# Marshmallow.net
KiCad netlist of a schematic drawn in EAGLE
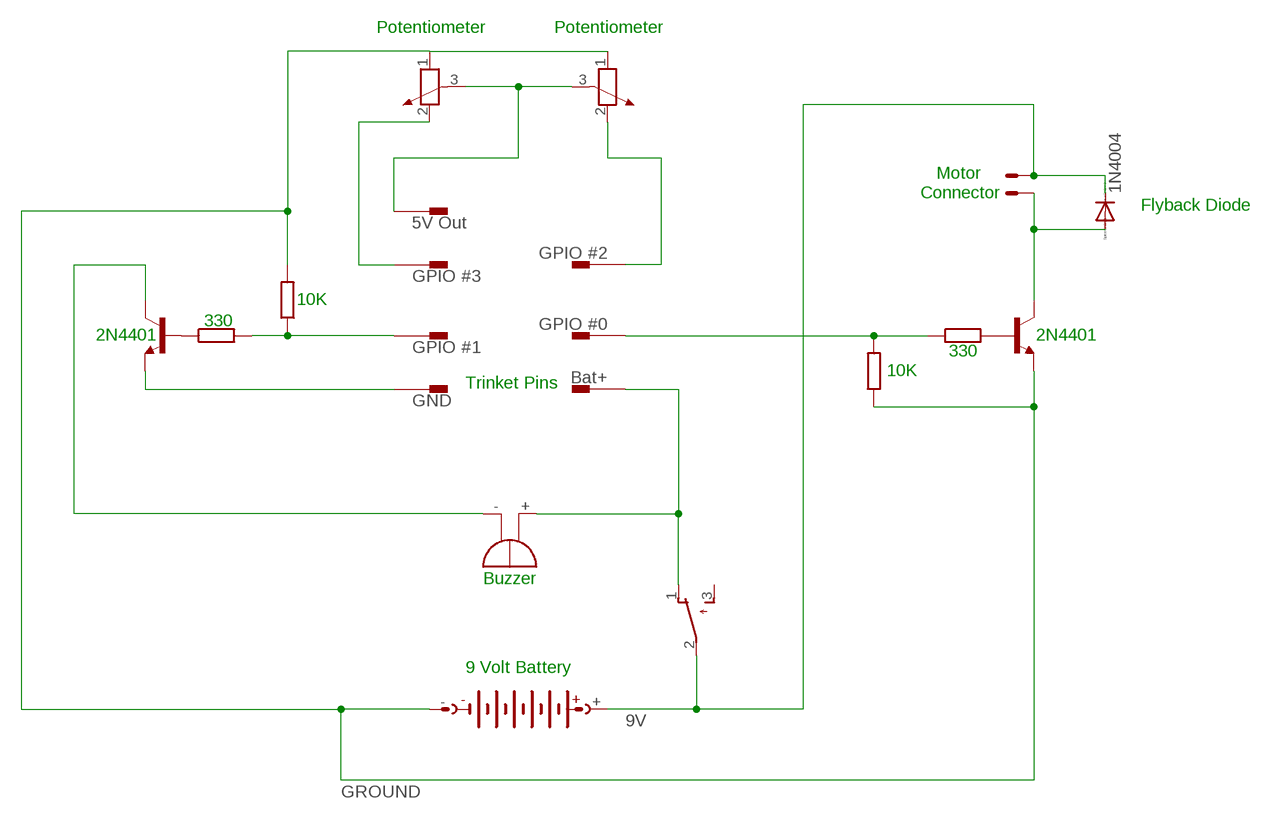
[diagram p0: schematic, sheet 1]

(export (version "E")
  (design (tool "Eeschema 10.0.6"))
  (components
    (comp (ref "D1")
      (value "1N4004")
      (footprint "eagle-import:DO41-10")
      (libsource (lib "eagle-import") (part "1N4004"))
    )
    (comp (ref "G1")
      (value "AB9V")
      (footprint "eagle-import:AB9V")
      (libsource (lib "eagle-import") (part "AB9V"))
    )
    (comp (ref "J1")
      (value "GPIO #1")
      (footprint "eagle-import:62221")
      (fields (field (name "MF") "TYCO ELECTRONICS") (field (name "MPN") "62221-1"))
      (libsource (lib "eagle-import") (part "PIN1-2"))
    )
    (comp (ref "J2")
      (value "GND")
      (footprint "eagle-import:62221")
      (fields (field (name "MF") "TYCO ELECTRONICS") (field (name "MPN") "62221-1"))
      (libsource (lib "eagle-import") (part "PIN1-2"))
    )
    (comp (ref "J3")
      (value "GPIO #0")
      (footprint "eagle-import:62221")
      (fields (field (name "MF") "TYCO ELECTRONICS") (field (name "MPN") "62221-1"))
      (libsource (lib "eagle-import") (part "PIN1-2"))
    )
    (comp (ref "J4")
      (value "Bat+")
      (footprint "eagle-import:62221")
      (fields (field (name "MF") "TYCO ELECTRONICS") (field (name "MPN") "62221-1"))
      (libsource (lib "eagle-import") (part "PIN1-2"))
    )
    (comp (ref "J5")
      (value "GPIO #2")
      (footprint "eagle-import:62221")
      (fields (field (name "MF") "TYCO ELECTRONICS") (field (name "MPN") "62221-1"))
      (libsource (lib "eagle-import") (part "PIN1-2"))
    )
    (comp (ref "J6")
      (value "GPIO #3")
      (footprint "eagle-import:62221")
      (fields (field (name "MF") "TYCO ELECTRONICS") (field (name "MPN") "62221-1"))
      (libsource (lib "eagle-import") (part "PIN1-2"))
    )
    (comp (ref "J7")
      (value "5V Out")
      (footprint "eagle-import:62221")
      (fields (field (name "MF") "TYCO ELECTRONICS") (field (name "MPN") "62221-1"))
      (libsource (lib "eagle-import") (part "PIN1-2"))
    )
    (comp (ref "R5")
      (value "POTENTIOMETER_PT-10")
      (footprint "eagle-import:PT-10")
      (libsource (lib "eagle-import") (part "POTENTIOMETER_PT-10"))
    )
    (comp (ref "R6")
      (value "POTENTIOMETER_PT-10")
      (footprint "eagle-import:PT-10")
      (libsource (lib "eagle-import") (part "POTENTIOMETER_PT-10"))
    )
    (comp (ref "S1")
      (value "TL32PO")
      (footprint "eagle-import:TL3XPO")
      (libsource (lib "eagle-import") (part "TL32PO"))
    )
    (comp (ref "SG2")
      (value "F/BC35")
      (footprint "eagle-import:F_BC35")
      (libsource (lib "eagle-import") (part "F/BC35"))
    )
    (comp (ref "T1")
      (value "2N4401-NPN-TO92-EBC")
      (footprint "eagle-import:TO92-EBC")
      (libsource (lib "eagle-import") (part "-NPN-TO92-EBC2N4401"))
    )
    (comp (ref "T2")
      (value "2N4401-NPN-TO92-EBC")
      (footprint "eagle-import:TO92-EBC")
      (libsource (lib "eagle-import") (part "-NPN-TO92-EBC2N4401"))
    )
    (comp (ref "X2")
      (value "22-23-2021")
      (footprint "eagle-import:22-23-2021")
      (fields (field (name "MF") "MOLEX"))
      (libsource (lib "eagle-import") (part "22-23-2021"))
    )
  )
  (nets
    (net (code "1") (name "/9V") (class "Default")
      (node (ref "D1") (pin "C") (pinfunction "C_C") (pintype "passive"))
      (node (ref "G1") (pin "+") (pinfunction "+_+") (pintype "passive"))
      (node (ref "S1") (pin "2") (pinfunction "P_2") (pintype "passive"))
      (node (ref "X2") (pin "2") (pinfunction "S_2") (pintype "passive"))
    )
    (net (code "2") (name "/GROUND") (class "Default")
      (node (ref "G1") (pin "-") (pinfunction "-_-") (pintype "passive"))
      (node (ref "R5") (pin "1") (pinfunction "1_1") (pintype "passive"))
      (node (ref "R6") (pin "1") (pinfunction "1_1") (pintype "passive"))
      (node (ref "T1") (pin "E") (pinfunction "E_E") (pintype "passive"))
    )
    (net (code "3") (name "Net-(J2-Pad1)") (class "Default")
      (node (ref "J2") (pin "1") (pinfunction "1_1") (pintype "passive"))
      (node (ref "T2") (pin "E") (pinfunction "E_E") (pintype "passive"))
    )
    (net (code "4") (name "Net-(J5-Pad1)") (class "Default")
      (node (ref "J5") (pin "1") (pinfunction "1_1") (pintype "passive"))
      (node (ref "R6") (pin "2") (pinfunction "2_2") (pintype "passive"))
    )
    (net (code "5") (name "Net-(J6-Pad1)") (class "Default")
      (node (ref "J6") (pin "1") (pinfunction "1_1") (pintype "passive"))
      (node (ref "R5") (pin "2") (pinfunction "2_2") (pintype "passive"))
    )
    (net (code "6") (name "Net-(J7-Pad1)") (class "Default")
      (node (ref "J7") (pin "1") (pinfunction "1_1") (pintype "passive"))
      (node (ref "R5") (pin "3") (pinfunction "3_3") (pintype "passive"))
      (node (ref "R6") (pin "3") (pinfunction "3_3") (pintype "passive"))
    )
    (net (code "7") (name "Net-(S1-O)") (class "Default")
      (node (ref "J4") (pin "1") (pinfunction "1_1") (pintype "passive"))
      (node (ref "S1") (pin "1") (pinfunction "O_1") (pintype "passive"))
      (node (ref "SG2") (pin "+") (pinfunction "+_+") (pintype "passive"))
    )
    (net (code "8") (name "Net-(SG2-Pad-)") (class "Default")
      (node (ref "SG2") (pin "-") (pinfunction "-_-") (pintype "passive"))
      (node (ref "T2") (pin "C") (pinfunction "C_C") (pintype "passive"))
    )
    (net (code "9") (name "Net-(X2A-S)") (class "Default")
      (node (ref "D1") (pin "A") (pinfunction "A_A") (pintype "passive"))
      (node (ref "T1") (pin "C") (pinfunction "C_C") (pintype "passive"))
      (node (ref "X2") (pin "1") (pinfunction "S_1") (pintype "passive"))
    )
    (net (code "10") (name "unconnected-(J1-Pad1)") (class "Default")
      (node (ref "J1") (pin "1") (pinfunction "1_1") (pintype "passive"))
    )
    (net (code "11") (name "unconnected-(J3-Pad1)") (class "Default")
      (node (ref "J3") (pin "1") (pinfunction "1_1") (pintype "passive"))
    )
    (net (code "12") (name "unconnected-(S1-S-Pad3)") (class "Default")
      (node (ref "S1") (pin "3") (pinfunction "S_3") (pintype "passive"))
    )
    (net (code "13") (name "unconnected-(T1-PadB)") (class "Default")
      (node (ref "T1") (pin "B") (pinfunction "B_B") (pintype "passive"))
    )
    (net (code "14") (name "unconnected-(T2-PadB)") (class "Default")
      (node (ref "T2") (pin "B") (pinfunction "B_B") (pintype "passive"))
    )
  )
)
